# Audio_panel_board.net
KiCad netlist of a schematic drawn in EAGLE
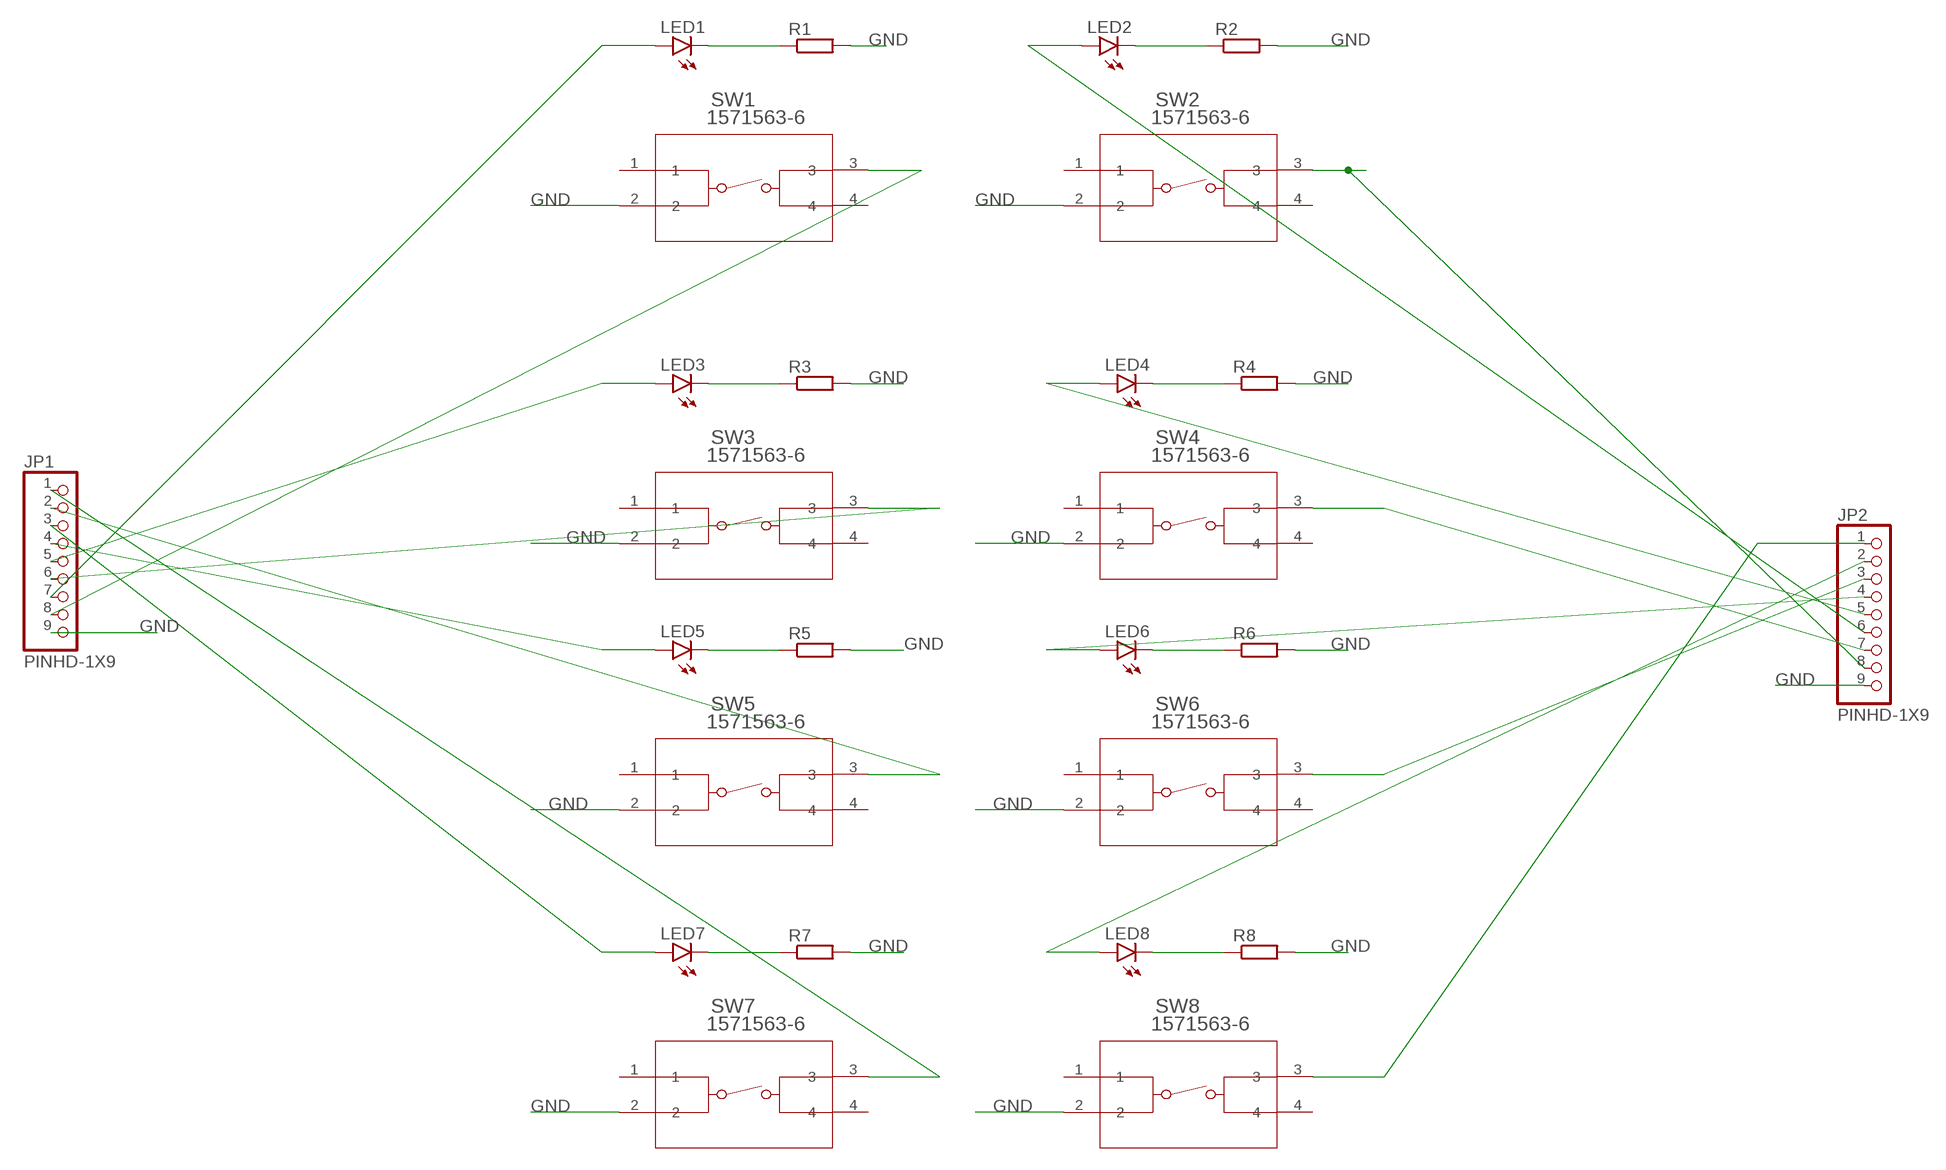
[diagram p0: schematic, sheet 1, part 1 of 2]
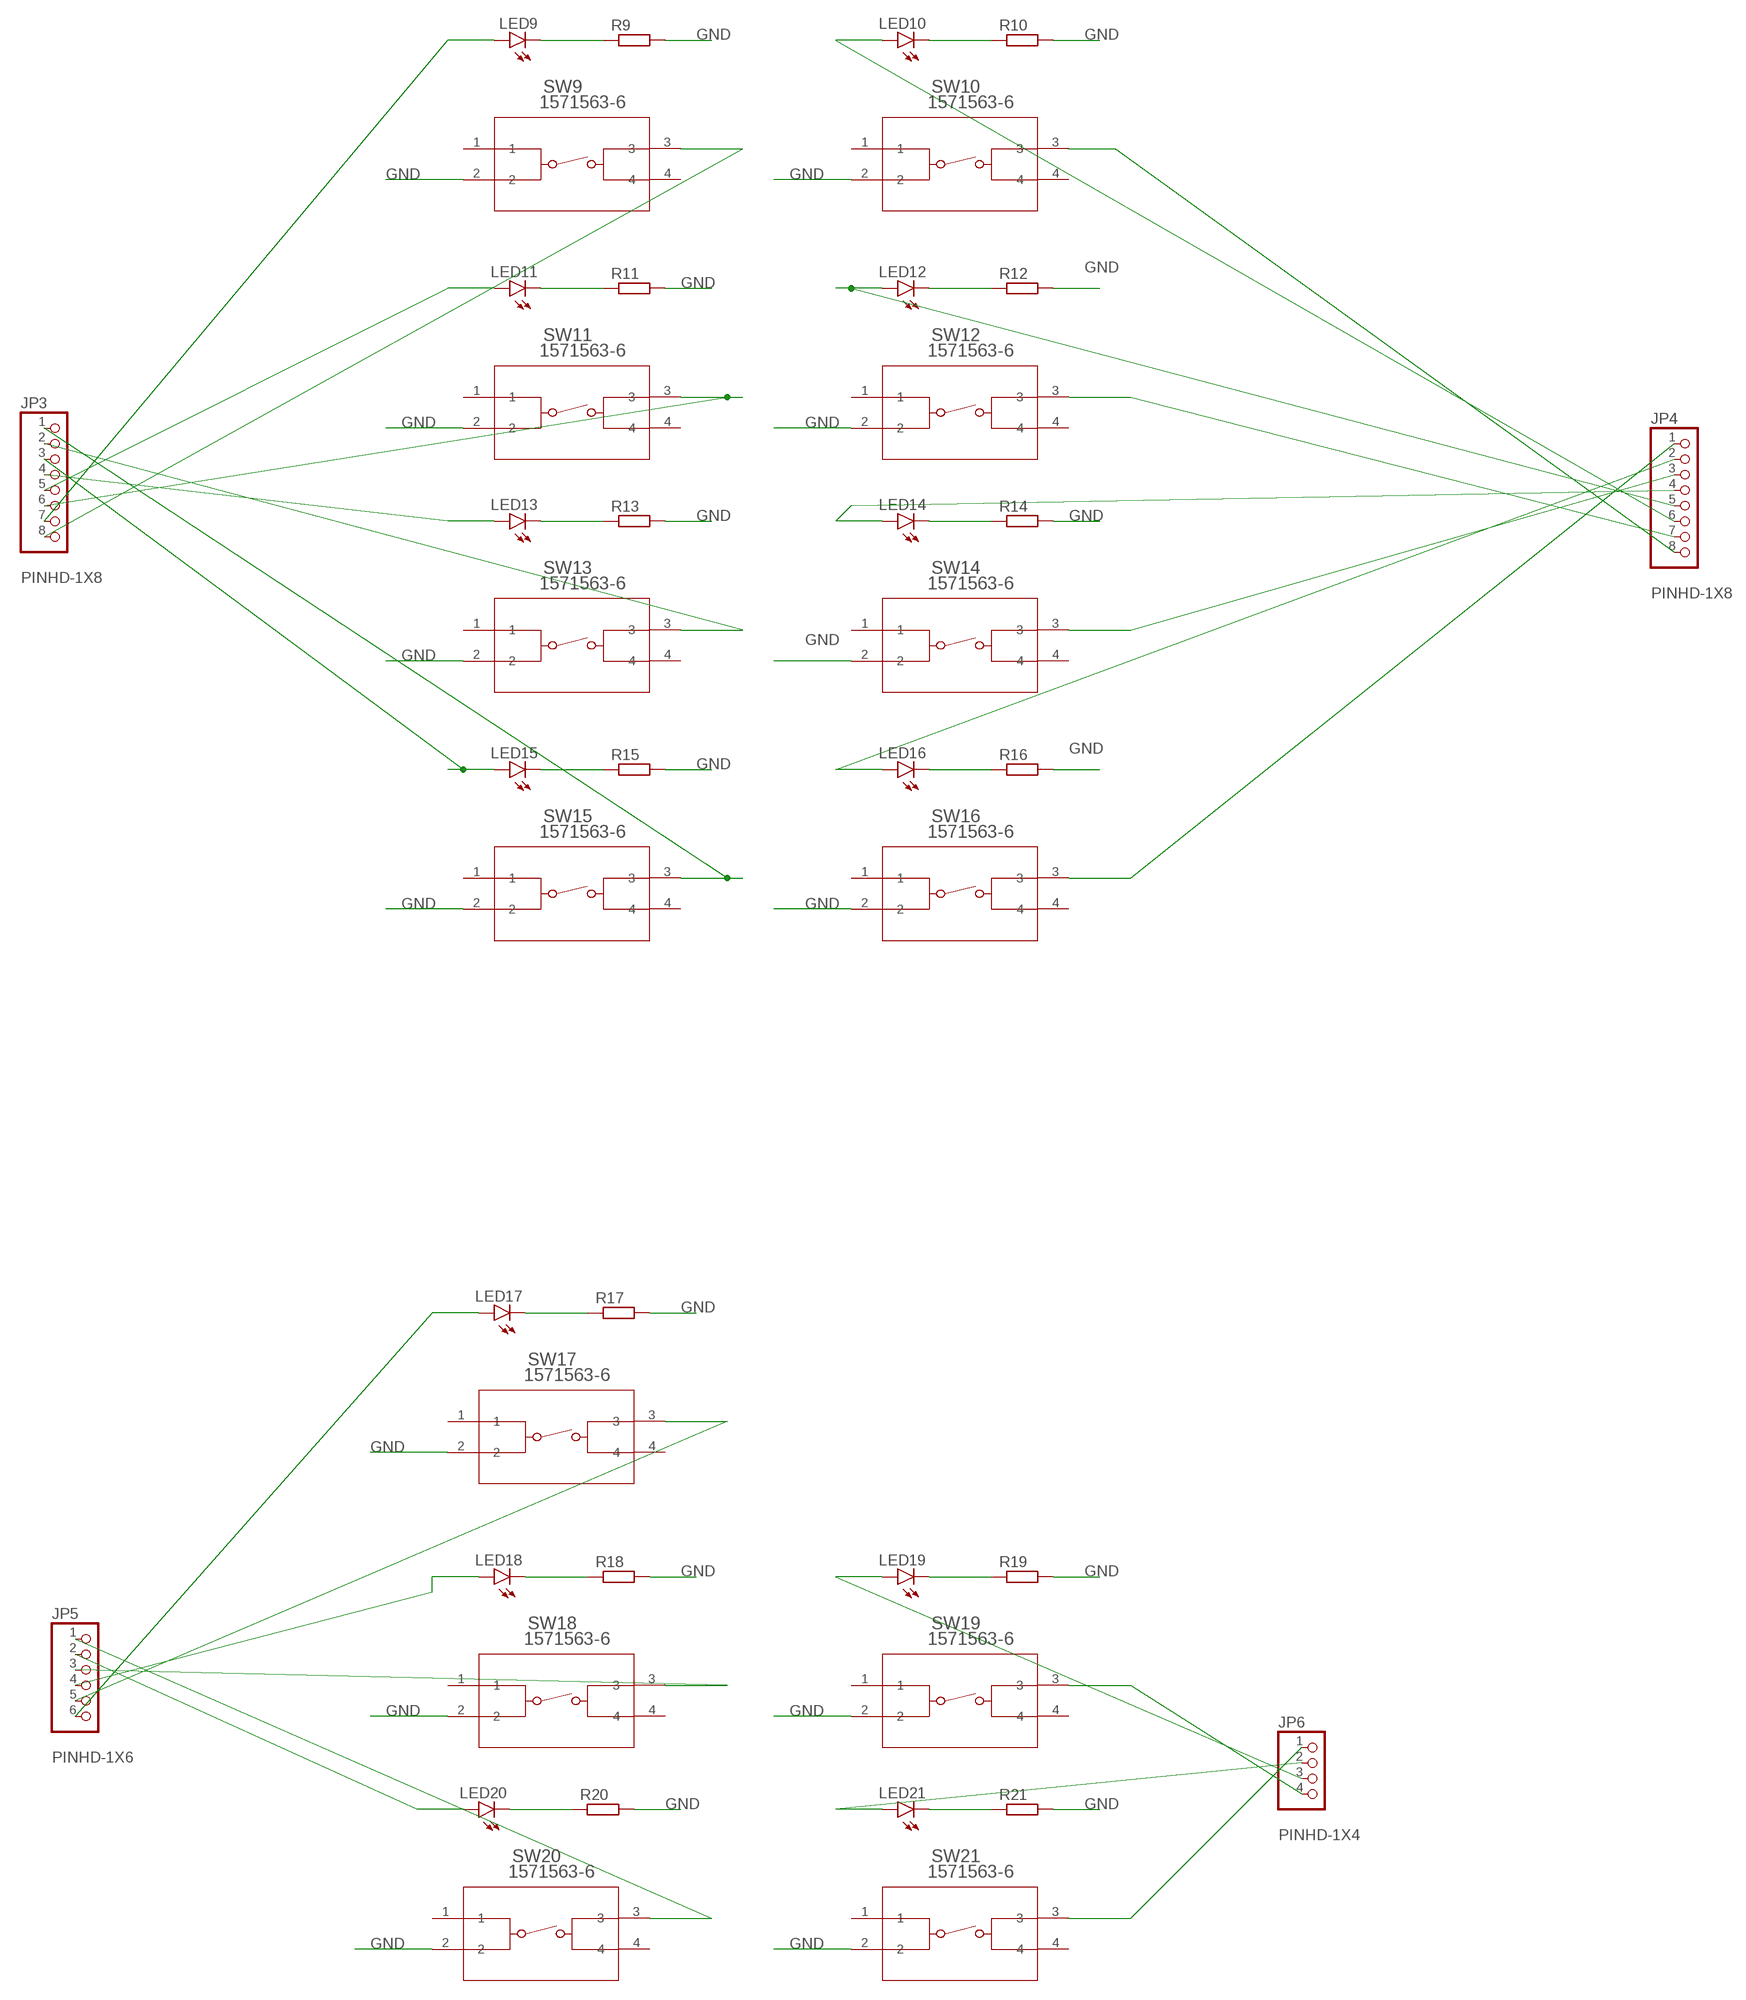
[diagram p1: schematic, sheet 1, part 2 of 2]

(export (version "E")
  (design (tool "Eeschema 10.0.6"))
  (components
    (comp (ref "JP1")
      (value "PINHD-1X9")
      (footprint "eagle-import:1X09")
      (libsource (lib "eagle-import") (part "PINHD-1X9"))
    )
    (comp (ref "JP2")
      (value "PINHD-1X9")
      (footprint "eagle-import:1X09")
      (libsource (lib "eagle-import") (part "PINHD-1X9"))
    )
    (comp (ref "JP3")
      (value "PINHD-1X8")
      (footprint "eagle-import:1X08")
      (libsource (lib "eagle-import") (part "PINHD-1X8"))
    )
    (comp (ref "JP4")
      (value "PINHD-1X8")
      (footprint "eagle-import:1X08")
      (libsource (lib "eagle-import") (part "PINHD-1X8"))
    )
    (comp (ref "JP5")
      (value "PINHD-1X6")
      (footprint "eagle-import:1X06")
      (libsource (lib "eagle-import") (part "PINHD-1X6"))
    )
    (comp (ref "JP6")
      (value "PINHD-1X4")
      (footprint "eagle-import:1X04")
      (libsource (lib "eagle-import") (part "PINHD-1X4"))
    )
    (comp (ref "LED1")
      (value "LEDCHIP-LED0805")
      (footprint "eagle-import:CHIP-LED0805")
      (libsource (lib "eagle-import") (part "LEDCHIP-LED0805"))
    )
    (comp (ref "LED2")
      (value "LEDCHIP-LED0805")
      (footprint "eagle-import:CHIP-LED0805")
      (libsource (lib "eagle-import") (part "LEDCHIP-LED0805"))
    )
    (comp (ref "LED3")
      (value "LEDCHIP-LED0805")
      (footprint "eagle-import:CHIP-LED0805")
      (libsource (lib "eagle-import") (part "LEDCHIP-LED0805"))
    )
    (comp (ref "LED4")
      (value "LEDCHIP-LED0805")
      (footprint "eagle-import:CHIP-LED0805")
      (libsource (lib "eagle-import") (part "LEDCHIP-LED0805"))
    )
    (comp (ref "LED5")
      (value "LEDCHIP-LED0805")
      (footprint "eagle-import:CHIP-LED0805")
      (libsource (lib "eagle-import") (part "LEDCHIP-LED0805"))
    )
    (comp (ref "LED6")
      (value "LEDCHIP-LED0805")
      (footprint "eagle-import:CHIP-LED0805")
      (libsource (lib "eagle-import") (part "LEDCHIP-LED0805"))
    )
    (comp (ref "LED7")
      (value "LEDCHIP-LED0805")
      (footprint "eagle-import:CHIP-LED0805")
      (libsource (lib "eagle-import") (part "LEDCHIP-LED0805"))
    )
    (comp (ref "LED8")
      (value "LEDCHIP-LED0805")
      (footprint "eagle-import:CHIP-LED0805")
      (libsource (lib "eagle-import") (part "LEDCHIP-LED0805"))
    )
    (comp (ref "LED9")
      (value "LEDCHIP-LED0805")
      (footprint "eagle-import:CHIP-LED0805")
      (libsource (lib "eagle-import") (part "LEDCHIP-LED0805"))
    )
    (comp (ref "LED10")
      (value "LEDCHIP-LED0805")
      (footprint "eagle-import:CHIP-LED0805")
      (libsource (lib "eagle-import") (part "LEDCHIP-LED0805"))
    )
    (comp (ref "LED11")
      (value "LEDCHIP-LED0805")
      (footprint "eagle-import:CHIP-LED0805")
      (libsource (lib "eagle-import") (part "LEDCHIP-LED0805"))
    )
    (comp (ref "LED12")
      (value "LEDCHIP-LED0805")
      (footprint "eagle-import:CHIP-LED0805")
      (libsource (lib "eagle-import") (part "LEDCHIP-LED0805"))
    )
    (comp (ref "LED13")
      (value "LEDCHIP-LED0805")
      (footprint "eagle-import:CHIP-LED0805")
      (libsource (lib "eagle-import") (part "LEDCHIP-LED0805"))
    )
    (comp (ref "LED14")
      (value "LEDCHIP-LED0805")
      (footprint "eagle-import:CHIP-LED0805")
      (libsource (lib "eagle-import") (part "LEDCHIP-LED0805"))
    )
    (comp (ref "LED15")
      (value "LEDCHIP-LED0805")
      (footprint "eagle-import:CHIP-LED0805")
      (libsource (lib "eagle-import") (part "LEDCHIP-LED0805"))
    )
    (comp (ref "LED16")
      (value "LEDCHIP-LED0805")
      (footprint "eagle-import:CHIP-LED0805")
      (libsource (lib "eagle-import") (part "LEDCHIP-LED0805"))
    )
    (comp (ref "LED17")
      (value "LEDCHIP-LED0805")
      (footprint "eagle-import:CHIP-LED0805")
      (libsource (lib "eagle-import") (part "LEDCHIP-LED0805"))
    )
    (comp (ref "LED18")
      (value "LEDCHIP-LED0805")
      (footprint "eagle-import:CHIP-LED0805")
      (libsource (lib "eagle-import") (part "LEDCHIP-LED0805"))
    )
    (comp (ref "LED19")
      (value "LEDCHIP-LED0805")
      (footprint "eagle-import:CHIP-LED0805")
      (libsource (lib "eagle-import") (part "LEDCHIP-LED0805"))
    )
    (comp (ref "LED20")
      (value "LEDCHIP-LED0805")
      (footprint "eagle-import:CHIP-LED0805")
      (libsource (lib "eagle-import") (part "LEDCHIP-LED0805"))
    )
    (comp (ref "LED21")
      (value "LEDCHIP-LED0805")
      (footprint "eagle-import:CHIP-LED0805")
      (libsource (lib "eagle-import") (part "LEDCHIP-LED0805"))
    )
    (comp (ref "R1")
      (value "R-EU_R1206")
      (footprint "eagle-import:R1206")
      (libsource (lib "eagle-import") (part "R-EU_R1206"))
    )
    (comp (ref "R2")
      (value "R-EU_R1206")
      (footprint "eagle-import:R1206")
      (libsource (lib "eagle-import") (part "R-EU_R1206"))
    )
    (comp (ref "R3")
      (value "R-EU_R1206")
      (footprint "eagle-import:R1206")
      (libsource (lib "eagle-import") (part "R-EU_R1206"))
    )
    (comp (ref "R4")
      (value "R-EU_R1206")
      (footprint "eagle-import:R1206")
      (libsource (lib "eagle-import") (part "R-EU_R1206"))
    )
    (comp (ref "R5")
      (value "R-EU_R1206")
      (footprint "eagle-import:R1206")
      (libsource (lib "eagle-import") (part "R-EU_R1206"))
    )
    (comp (ref "R6")
      (value "R-EU_R1206")
      (footprint "eagle-import:R1206")
      (libsource (lib "eagle-import") (part "R-EU_R1206"))
    )
    (comp (ref "R7")
      (value "R-EU_R1206")
      (footprint "eagle-import:R1206")
      (libsource (lib "eagle-import") (part "R-EU_R1206"))
    )
    (comp (ref "R8")
      (value "R-EU_R1206")
      (footprint "eagle-import:R1206")
      (libsource (lib "eagle-import") (part "R-EU_R1206"))
    )
    (comp (ref "R9")
      (value "R-EU_R1206")
      (footprint "eagle-import:R1206")
      (libsource (lib "eagle-import") (part "R-EU_R1206"))
    )
    (comp (ref "R10")
      (value "R-EU_R1206")
      (footprint "eagle-import:R1206")
      (libsource (lib "eagle-import") (part "R-EU_R1206"))
    )
    (comp (ref "R11")
      (value "R-EU_R1206")
      (footprint "eagle-import:R1206")
      (libsource (lib "eagle-import") (part "R-EU_R1206"))
    )
    (comp (ref "R12")
      (value "R-EU_R1206")
      (footprint "eagle-import:R1206")
      (libsource (lib "eagle-import") (part "R-EU_R1206"))
    )
    (comp (ref "R13")
      (value "R-EU_R1206")
      (footprint "eagle-import:R1206")
      (libsource (lib "eagle-import") (part "R-EU_R1206"))
    )
    (comp (ref "R14")
      (value "R-EU_R1206")
      (footprint "eagle-import:R1206")
      (libsource (lib "eagle-import") (part "R-EU_R1206"))
    )
    (comp (ref "R15")
      (value "R-EU_R1206")
      (footprint "eagle-import:R1206")
      (libsource (lib "eagle-import") (part "R-EU_R1206"))
    )
    (comp (ref "R16")
      (value "R-EU_R1206")
      (footprint "eagle-import:R1206")
      (libsource (lib "eagle-import") (part "R-EU_R1206"))
    )
    (comp (ref "R17")
      (value "R-EU_R1206")
      (footprint "eagle-import:R1206")
      (libsource (lib "eagle-import") (part "R-EU_R1206"))
    )
    (comp (ref "R18")
      (value "R-EU_R1206")
      (footprint "eagle-import:R1206")
      (libsource (lib "eagle-import") (part "R-EU_R1206"))
    )
    (comp (ref "R19")
      (value "R-EU_R1206")
      (footprint "eagle-import:R1206")
      (libsource (lib "eagle-import") (part "R-EU_R1206"))
    )
    (comp (ref "R20")
      (value "R-EU_R1206")
      (footprint "eagle-import:R1206")
      (libsource (lib "eagle-import") (part "R-EU_R1206"))
    )
    (comp (ref "R21")
      (value "R-EU_R1206")
      (footprint "eagle-import:R1206")
      (libsource (lib "eagle-import") (part "R-EU_R1206"))
    )
    (comp (ref "SW1")
      (value "1571563-6")
      (footprint "eagle-import:SW4_1437565-E")
      (fields (field (name "COPYRIGHT") "Copyright (C) 2016 Accelerated Designs. All rights reserved"))
      (libsource (lib "eagle-import") (part "1571563-6"))
    )
    (comp (ref "SW2")
      (value "1571563-6")
      (footprint "eagle-import:SW4_1437565-E")
      (fields (field (name "COPYRIGHT") "Copyright (C) 2016 Accelerated Designs. All rights reserved"))
      (libsource (lib "eagle-import") (part "1571563-6"))
    )
    (comp (ref "SW3")
      (value "1571563-6")
      (footprint "eagle-import:SW4_1437565-E")
      (fields (field (name "COPYRIGHT") "Copyright (C) 2016 Accelerated Designs. All rights reserved"))
      (libsource (lib "eagle-import") (part "1571563-6"))
    )
    (comp (ref "SW4")
      (value "1571563-6")
      (footprint "eagle-import:SW4_1437565-E")
      (fields (field (name "COPYRIGHT") "Copyright (C) 2016 Accelerated Designs. All rights reserved"))
      (libsource (lib "eagle-import") (part "1571563-6"))
    )
    (comp (ref "SW5")
      (value "1571563-6")
      (footprint "eagle-import:SW4_1437565-E")
      (fields (field (name "COPYRIGHT") "Copyright (C) 2016 Accelerated Designs. All rights reserved"))
      (libsource (lib "eagle-import") (part "1571563-6"))
    )
    (comp (ref "SW6")
      (value "1571563-6")
      (footprint "eagle-import:SW4_1437565-E")
      (fields (field (name "COPYRIGHT") "Copyright (C) 2016 Accelerated Designs. All rights reserved"))
      (libsource (lib "eagle-import") (part "1571563-6"))
    )
    (comp (ref "SW7")
      (value "1571563-6")
      (footprint "eagle-import:SW4_1437565-E")
      (fields (field (name "COPYRIGHT") "Copyright (C) 2016 Accelerated Designs. All rights reserved"))
      (libsource (lib "eagle-import") (part "1571563-6"))
    )
    (comp (ref "SW8")
      (value "1571563-6")
      (footprint "eagle-import:SW4_1437565-E")
      (fields (field (name "COPYRIGHT") "Copyright (C) 2016 Accelerated Designs. All rights reserved"))
      (libsource (lib "eagle-import") (part "1571563-6"))
    )
    (comp (ref "SW9")
      (value "1571563-6")
      (footprint "eagle-import:SW4_1437565-E")
      (fields (field (name "COPYRIGHT") "Copyright (C) 2016 Accelerated Designs. All rights reserved"))
      (libsource (lib "eagle-import") (part "1571563-6"))
    )
    (comp (ref "SW10")
      (value "1571563-6")
      (footprint "eagle-import:SW4_1437565-E")
      (fields (field (name "COPYRIGHT") "Copyright (C) 2016 Accelerated Designs. All rights reserved"))
      (libsource (lib "eagle-import") (part "1571563-6"))
    )
    (comp (ref "SW11")
      (value "1571563-6")
      (footprint "eagle-import:SW4_1437565-E")
      (fields (field (name "COPYRIGHT") "Copyright (C) 2016 Accelerated Designs. All rights reserved"))
      (libsource (lib "eagle-import") (part "1571563-6"))
    )
    (comp (ref "SW12")
      (value "1571563-6")
      (footprint "eagle-import:SW4_1437565-E")
      (fields (field (name "COPYRIGHT") "Copyright (C) 2016 Accelerated Designs. All rights reserved"))
      (libsource (lib "eagle-import") (part "1571563-6"))
    )
    (comp (ref "SW13")
      (value "1571563-6")
      (footprint "eagle-import:SW4_1437565-E")
      (fields (field (name "COPYRIGHT") "Copyright (C) 2016 Accelerated Designs. All rights reserved"))
      (libsource (lib "eagle-import") (part "1571563-6"))
    )
    (comp (ref "SW14")
      (value "1571563-6")
      (footprint "eagle-import:SW4_1437565-E")
      (fields (field (name "COPYRIGHT") "Copyright (C) 2016 Accelerated Designs. All rights reserved"))
      (libsource (lib "eagle-import") (part "1571563-6"))
    )
    (comp (ref "SW15")
      (value "1571563-6")
      (footprint "eagle-import:SW4_1437565-E")
      (fields (field (name "COPYRIGHT") "Copyright (C) 2016 Accelerated Designs. All rights reserved"))
      (libsource (lib "eagle-import") (part "1571563-6"))
    )
    (comp (ref "SW16")
      (value "1571563-6")
      (footprint "eagle-import:SW4_1437565-E")
      (fields (field (name "COPYRIGHT") "Copyright (C) 2016 Accelerated Designs. All rights reserved"))
      (libsource (lib "eagle-import") (part "1571563-6"))
    )
    (comp (ref "SW17")
      (value "1571563-6")
      (footprint "eagle-import:SW4_1437565-E")
      (fields (field (name "COPYRIGHT") "Copyright (C) 2016 Accelerated Designs. All rights reserved"))
      (libsource (lib "eagle-import") (part "1571563-6"))
    )
    (comp (ref "SW18")
      (value "1571563-6")
      (footprint "eagle-import:SW4_1437565-E")
      (fields (field (name "COPYRIGHT") "Copyright (C) 2016 Accelerated Designs. All rights reserved"))
      (libsource (lib "eagle-import") (part "1571563-6"))
    )
    (comp (ref "SW19")
      (value "1571563-6")
      (footprint "eagle-import:SW4_1437565-E")
      (fields (field (name "COPYRIGHT") "Copyright (C) 2016 Accelerated Designs. All rights reserved"))
      (libsource (lib "eagle-import") (part "1571563-6"))
    )
    (comp (ref "SW20")
      (value "1571563-6")
      (footprint "eagle-import:SW4_1437565-E")
      (fields (field (name "COPYRIGHT") "Copyright (C) 2016 Accelerated Designs. All rights reserved"))
      (libsource (lib "eagle-import") (part "1571563-6"))
    )
    (comp (ref "SW21")
      (value "1571563-6")
      (footprint "eagle-import:SW4_1437565-E")
      (fields (field (name "COPYRIGHT") "Copyright (C) 2016 Accelerated Designs. All rights reserved"))
      (libsource (lib "eagle-import") (part "1571563-6"))
    )
  )
  (nets
    (net (code "1") (name "/GND") (class "Default")
      (node (ref "JP1") (pin "9") (pinfunction "9_9") (pintype "passive"))
      (node (ref "JP2") (pin "9") (pinfunction "9_9") (pintype "passive"))
      (node (ref "R1") (pin "2") (pinfunction "2_2") (pintype "passive"))
      (node (ref "R10") (pin "2") (pinfunction "2_2") (pintype "passive"))
      (node (ref "R11") (pin "2") (pinfunction "2_2") (pintype "passive"))
      (node (ref "R12") (pin "2") (pinfunction "2_2") (pintype "passive"))
      (node (ref "R13") (pin "2") (pinfunction "2_2") (pintype "passive"))
      (node (ref "R14") (pin "2") (pinfunction "2_2") (pintype "passive"))
      (node (ref "R15") (pin "2") (pinfunction "2_2") (pintype "passive"))
      (node (ref "R16") (pin "2") (pinfunction "2_2") (pintype "passive"))
      (node (ref "R17") (pin "2") (pinfunction "2_2") (pintype "passive"))
      (node (ref "R18") (pin "2") (pinfunction "2_2") (pintype "passive"))
      (node (ref "R19") (pin "2") (pinfunction "2_2") (pintype "passive"))
      (node (ref "R2") (pin "2") (pinfunction "2_2") (pintype "passive"))
      (node (ref "R20") (pin "2") (pinfunction "2_2") (pintype "passive"))
      (node (ref "R21") (pin "2") (pinfunction "2_2") (pintype "passive"))
      (node (ref "R3") (pin "2") (pinfunction "2_2") (pintype "passive"))
      (node (ref "R4") (pin "2") (pinfunction "2_2") (pintype "passive"))
      (node (ref "R5") (pin "2") (pinfunction "2_2") (pintype "passive"))
      (node (ref "R6") (pin "2") (pinfunction "2_2") (pintype "passive"))
      (node (ref "R7") (pin "2") (pinfunction "2_2") (pintype "passive"))
      (node (ref "R8") (pin "2") (pinfunction "2_2") (pintype "passive"))
      (node (ref "R9") (pin "2") (pinfunction "2_2") (pintype "passive"))
      (node (ref "SW1") (pin "2") (pinfunction "2_2") (pintype "passive"))
      (node (ref "SW10") (pin "2") (pinfunction "2_2") (pintype "passive"))
      (node (ref "SW11") (pin "2") (pinfunction "2_2") (pintype "passive"))
      (node (ref "SW12") (pin "2") (pinfunction "2_2") (pintype "passive"))
      (node (ref "SW13") (pin "2") (pinfunction "2_2") (pintype "passive"))
      (node (ref "SW14") (pin "2") (pinfunction "2_2") (pintype "passive"))
      (node (ref "SW15") (pin "2") (pinfunction "2_2") (pintype "passive"))
      (node (ref "SW16") (pin "2") (pinfunction "2_2") (pintype "passive"))
      (node (ref "SW17") (pin "2") (pinfunction "2_2") (pintype "passive"))
      (node (ref "SW18") (pin "2") (pinfunction "2_2") (pintype "passive"))
      (node (ref "SW19") (pin "2") (pinfunction "2_2") (pintype "passive"))
      (node (ref "SW2") (pin "2") (pinfunction "2_2") (pintype "passive"))
      (node (ref "SW20") (pin "2") (pinfunction "2_2") (pintype "passive"))
      (node (ref "SW21") (pin "2") (pinfunction "2_2") (pintype "passive"))
      (node (ref "SW3") (pin "2") (pinfunction "2_2") (pintype "passive"))
      (node (ref "SW4") (pin "2") (pinfunction "2_2") (pintype "passive"))
      (node (ref "SW5") (pin "2") (pinfunction "2_2") (pintype "passive"))
      (node (ref "SW6") (pin "2") (pinfunction "2_2") (pintype "passive"))
      (node (ref "SW7") (pin "2") (pinfunction "2_2") (pintype "passive"))
      (node (ref "SW8") (pin "2") (pinfunction "2_2") (pintype "passive"))
      (node (ref "SW9") (pin "2") (pinfunction "2_2") (pintype "passive"))
    )
    (net (code "2") (name "Net-(JP1-Pad1)") (class "Default")
      (node (ref "JP1") (pin "1") (pinfunction "1_1") (pintype "passive"))
      (node (ref "SW7") (pin "3") (pinfunction "3_3") (pintype "passive"))
    )
    (net (code "3") (name "Net-(JP1-Pad2)") (class "Default")
      (node (ref "JP1") (pin "2") (pinfunction "2_2") (pintype "passive"))
      (node (ref "SW5") (pin "3") (pinfunction "3_3") (pintype "passive"))
    )
    (net (code "4") (name "Net-(JP1-Pad3)") (class "Default")
      (node (ref "JP1") (pin "3") (pinfunction "3_3") (pintype "passive"))
      (node (ref "LED7") (pin "A") (pinfunction "A_A") (pintype "passive"))
    )
    (net (code "5") (name "Net-(JP1-Pad4)") (class "Default")
      (node (ref "JP1") (pin "4") (pinfunction "4_4") (pintype "passive"))
      (node (ref "LED5") (pin "A") (pinfunction "A_A") (pintype "passive"))
    )
    (net (code "6") (name "Net-(JP1-Pad5)") (class "Default")
      (node (ref "JP1") (pin "5") (pinfunction "5_5") (pintype "passive"))
      (node (ref "LED3") (pin "A") (pinfunction "A_A") (pintype "passive"))
    )
    (net (code "7") (name "Net-(JP1-Pad6)") (class "Default")
      (node (ref "JP1") (pin "6") (pinfunction "6_6") (pintype "passive"))
      (node (ref "SW3") (pin "3") (pinfunction "3_3") (pintype "passive"))
    )
    (net (code "8") (name "Net-(JP1-Pad7)") (class "Default")
      (node (ref "JP1") (pin "7") (pinfunction "7_7") (pintype "passive"))
      (node (ref "LED1") (pin "A") (pinfunction "A_A") (pintype "passive"))
    )
    (net (code "9") (name "Net-(JP1-Pad8)") (class "Default")
      (node (ref "JP1") (pin "8") (pinfunction "8_8") (pintype "passive"))
      (node (ref "SW1") (pin "3") (pinfunction "3_3") (pintype "passive"))
    )
    (net (code "10") (name "Net-(JP2-Pad1)") (class "Default")
      (node (ref "JP2") (pin "1") (pinfunction "1_1") (pintype "passive"))
      (node (ref "SW8") (pin "3") (pinfunction "3_3") (pintype "passive"))
    )
    (net (code "11") (name "Net-(JP2-Pad2)") (class "Default")
      (node (ref "JP2") (pin "2") (pinfunction "2_2") (pintype "passive"))
      (node (ref "LED8") (pin "A") (pinfunction "A_A") (pintype "passive"))
    )
    (net (code "12") (name "Net-(JP2-Pad3)") (class "Default")
      (node (ref "JP2") (pin "3") (pinfunction "3_3") (pintype "passive"))
      (node (ref "SW6") (pin "3") (pinfunction "3_3") (pintype "passive"))
    )
    (net (code "13") (name "Net-(JP2-Pad4)") (class "Default")
      (node (ref "JP2") (pin "4") (pinfunction "4_4") (pintype "passive"))
      (node (ref "LED6") (pin "A") (pinfunction "A_A") (pintype "passive"))
    )
    (net (code "14") (name "Net-(JP2-Pad5)") (class "Default")
      (node (ref "JP2") (pin "5") (pinfunction "5_5") (pintype "passive"))
      (node (ref "LED4") (pin "A") (pinfunction "A_A") (pintype "passive"))
    )
    (net (code "15") (name "Net-(JP2-Pad6)") (class "Default")
      (node (ref "JP2") (pin "6") (pinfunction "6_6") (pintype "passive"))
      (node (ref "LED2") (pin "A") (pinfunction "A_A") (pintype "passive"))
    )
    (net (code "16") (name "Net-(JP2-Pad7)") (class "Default")
      (node (ref "JP2") (pin "7") (pinfunction "7_7") (pintype "passive"))
      (node (ref "SW4") (pin "3") (pinfunction "3_3") (pintype "passive"))
    )
    (net (code "17") (name "Net-(JP2-Pad8)") (class "Default")
      (node (ref "JP2") (pin "8") (pinfunction "8_8") (pintype "passive"))
      (node (ref "SW2") (pin "3") (pinfunction "3_3") (pintype "passive"))
    )
    (net (code "18") (name "Net-(JP3-Pad1)") (class "Default")
      (node (ref "JP3") (pin "1") (pinfunction "1_1") (pintype "passive"))
      (node (ref "SW15") (pin "3") (pinfunction "3_3") (pintype "passive"))
    )
    (net (code "19") (name "Net-(JP3-Pad2)") (class "Default")
      (node (ref "JP3") (pin "2") (pinfunction "2_2") (pintype "passive"))
      (node (ref "SW13") (pin "3") (pinfunction "3_3") (pintype "passive"))
    )
    (net (code "20") (name "Net-(JP3-Pad3)") (class "Default")
      (node (ref "JP3") (pin "3") (pinfunction "3_3") (pintype "passive"))
      (node (ref "LED15") (pin "A") (pinfunction "A_A") (pintype "passive"))
    )
    (net (code "21") (name "Net-(JP3-Pad4)") (class "Default")
      (node (ref "JP3") (pin "4") (pinfunction "4_4") (pintype "passive"))
      (node (ref "LED13") (pin "A") (pinfunction "A_A") (pintype "passive"))
    )
    (net (code "22") (name "Net-(JP3-Pad5)") (class "Default")
      (node (ref "JP3") (pin "5") (pinfunction "5_5") (pintype "passive"))
      (node (ref "LED11") (pin "A") (pinfunction "A_A") (pintype "passive"))
    )
    (net (code "23") (name "Net-(JP3-Pad6)") (class "Default")
      (node (ref "JP3") (pin "6") (pinfunction "6_6") (pintype "passive"))
      (node (ref "SW11") (pin "3") (pinfunction "3_3") (pintype "passive"))
    )
    (net (code "24") (name "Net-(JP3-Pad7)") (class "Default")
      (node (ref "JP3") (pin "7") (pinfunction "7_7") (pintype "passive"))
      (node (ref "LED9") (pin "A") (pinfunction "A_A") (pintype "passive"))
    )
    (net (code "25") (name "Net-(JP3-Pad8)") (class "Default")
      (node (ref "JP3") (pin "8") (pinfunction "8_8") (pintype "passive"))
      (node (ref "SW9") (pin "3") (pinfunction "3_3") (pintype "passive"))
    )
    (net (code "26") (name "Net-(JP4-Pad1)") (class "Default")
      (node (ref "JP4") (pin "1") (pinfunction "1_1") (pintype "passive"))
      (node (ref "SW16") (pin "3") (pinfunction "3_3") (pintype "passive"))
    )
    (net (code "27") (name "Net-(JP4-Pad2)") (class "Default")
      (node (ref "JP4") (pin "2") (pinfunction "2_2") (pintype "passive"))
      (node (ref "LED16") (pin "A") (pinfunction "A_A") (pintype "passive"))
    )
    (net (code "28") (name "Net-(JP4-Pad3)") (class "Default")
      (node (ref "JP4") (pin "3") (pinfunction "3_3") (pintype "passive"))
      (node (ref "SW14") (pin "3") (pinfunction "3_3") (pintype "passive"))
    )
    (net (code "29") (name "Net-(JP4-Pad4)") (class "Default")
      (node (ref "JP4") (pin "4") (pinfunction "4_4") (pintype "passive"))
      (node (ref "LED14") (pin "A") (pinfunction "A_A") (pintype "passive"))
    )
    (net (code "30") (name "Net-(JP4-Pad5)") (class "Default")
      (node (ref "JP4") (pin "5") (pinfunction "5_5") (pintype "passive"))
      (node (ref "LED12") (pin "A") (pinfunction "A_A") (pintype "passive"))
    )
    (net (code "31") (name "Net-(JP4-Pad6)") (class "Default")
      (node (ref "JP4") (pin "6") (pinfunction "6_6") (pintype "passive"))
      (node (ref "LED10") (pin "A") (pinfunction "A_A") (pintype "passive"))
    )
    (net (code "32") (name "Net-(JP4-Pad7)") (class "Default")
      (node (ref "JP4") (pin "7") (pinfunction "7_7") (pintype "passive"))
      (node (ref "SW12") (pin "3") (pinfunction "3_3") (pintype "passive"))
    )
    (net (code "33") (name "Net-(JP4-Pad8)") (class "Default")
      (node (ref "JP4") (pin "8") (pinfunction "8_8") (pintype "passive"))
      (node (ref "SW10") (pin "3") (pinfunction "3_3") (pintype "passive"))
    )
    (net (code "34") (name "Net-(JP5-Pad1)") (class "Default")
      (node (ref "JP5") (pin "1") (pinfunction "1_1") (pintype "passive"))
      (node (ref "SW20") (pin "3") (pinfunction "3_3") (pintype "passive"))
    )
    (net (code "35") (name "Net-(JP5-Pad2)") (class "Default")
      (node (ref "JP5") (pin "2") (pinfunction "2_2") (pintype "passive"))
      (node (ref "LED20") (pin "A") (pinfunction "A_A") (pintype "passive"))
    )
    (net (code "36") (name "Net-(JP5-Pad3)") (class "Default")
      (node (ref "JP5") (pin "3") (pinfunction "3_3") (pintype "passive"))
      (node (ref "SW18") (pin "3") (pinfunction "3_3") (pintype "passive"))
    )
    (net (code "37") (name "Net-(JP5-Pad4)") (class "Default")
      (node (ref "JP5") (pin "4") (pinfunction "4_4") (pintype "passive"))
      (node (ref "LED18") (pin "A") (pinfunction "A_A") (pintype "passive"))
    )
    (net (code "38") (name "Net-(JP5-Pad5)") (class "Default")
      (node (ref "JP5") (pin "5") (pinfunction "5_5") (pintype "passive"))
      (node (ref "SW17") (pin "3") (pinfunction "3_3") (pintype "passive"))
    )
    (net (code "39") (name "Net-(JP5-Pad6)") (class "Default")
      (node (ref "JP5") (pin "6") (pinfunction "6_6") (pintype "passive"))
      (node (ref "LED17") (pin "A") (pinfunction "A_A") (pintype "passive"))
    )
    (net (code "40") (name "Net-(JP6-Pad1)") (class "Default")
      (node (ref "JP6") (pin "1") (pinfunction "1_1") (pintype "passive"))
      (node (ref "SW21") (pin "3") (pinfunction "3_3") (pintype "passive"))
    )
    (net (code "41") (name "Net-(JP6-Pad2)") (class "Default")
      (node (ref "JP6") (pin "2") (pinfunction "2_2") (pintype "passive"))
      (node (ref "LED21") (pin "A") (pinfunction "A_A") (pintype "passive"))
    )
    (net (code "42") (name "Net-(JP6-Pad3)") (class "Default")
      (node (ref "JP6") (pin "3") (pinfunction "3_3") (pintype "passive"))
      (node (ref "LED19") (pin "A") (pinfunction "A_A") (pintype "passive"))
    )
    (net (code "43") (name "Net-(JP6-Pad4)") (class "Default")
      (node (ref "JP6") (pin "4") (pinfunction "4_4") (pintype "passive"))
      (node (ref "SW19") (pin "3") (pinfunction "3_3") (pintype "passive"))
    )
    (net (code "44") (name "Net-(LED1-PadC)") (class "Default")
      (node (ref "LED1") (pin "C") (pinfunction "C_C") (pintype "passive"))
      (node (ref "R1") (pin "1") (pinfunction "1_1") (pintype "passive"))
    )
    (net (code "45") (name "Net-(LED2-PadC)") (class "Default")
      (node (ref "LED2") (pin "C") (pinfunction "C_C") (pintype "passive"))
      (node (ref "R2") (pin "1") (pinfunction "1_1") (pintype "passive"))
    )
    (net (code "46") (name "Net-(LED3-PadC)") (class "Default")
      (node (ref "LED3") (pin "C") (pinfunction "C_C") (pintype "passive"))
      (node (ref "R3") (pin "1") (pinfunction "1_1") (pintype "passive"))
    )
    (net (code "47") (name "Net-(LED4-PadC)") (class "Default")
      (node (ref "LED4") (pin "C") (pinfunction "C_C") (pintype "passive"))
      (node (ref "R4") (pin "1") (pinfunction "1_1") (pintype "passive"))
    )
    (net (code "48") (name "Net-(LED5-PadC)") (class "Default")
      (node (ref "LED5") (pin "C") (pinfunction "C_C") (pintype "passive"))
      (node (ref "R5") (pin "1") (pinfunction "1_1") (pintype "passive"))
    )
    (net (code "49") (name "Net-(LED6-PadC)") (class "Default")
      (node (ref "LED6") (pin "C") (pinfunction "C_C") (pintype "passive"))
      (node (ref "R6") (pin "1") (pinfunction "1_1") (pintype "passive"))
    )
    (net (code "50") (name "Net-(LED7-PadC)") (class "Default")
      (node (ref "LED7") (pin "C") (pinfunction "C_C") (pintype "passive"))
      (node (ref "R7") (pin "1") (pinfunction "1_1") (pintype "passive"))
    )
    (net (code "51") (name "Net-(LED8-PadC)") (class "Default")
      (node (ref "LED8") (pin "C") (pinfunction "C_C") (pintype "passive"))
      (node (ref "R8") (pin "1") (pinfunction "1_1") (pintype "passive"))
    )
    (net (code "52") (name "Net-(LED9-PadC)") (class "Default")
      (node (ref "LED9") (pin "C") (pinfunction "C_C") (pintype "passive"))
      (node (ref "R9") (pin "1") (pinfunction "1_1") (pintype "passive"))
    )
    (net (code "53") (name "Net-(LED10-PadC)") (class "Default")
      (node (ref "LED10") (pin "C") (pinfunction "C_C") (pintype "passive"))
      (node (ref "R10") (pin "1") (pinfunction "1_1") (pintype "passive"))
    )
    (net (code "54") (name "Net-(LED11-PadC)") (class "Default")
      (node (ref "LED11") (pin "C") (pinfunction "C_C") (pintype "passive"))
      (node (ref "R11") (pin "1") (pinfunction "1_1") (pintype "passive"))
    )
    (net (code "55") (name "Net-(LED12-PadC)") (class "Default")
      (node (ref "LED12") (pin "C") (pinfunction "C_C") (pintype "passive"))
      (node (ref "R12") (pin "1") (pinfunction "1_1") (pintype "passive"))
    )
    (net (code "56") (name "Net-(LED13-PadC)") (class "Default")
      (node (ref "LED13") (pin "C") (pinfunction "C_C") (pintype "passive"))
      (node (ref "R13") (pin "1") (pinfunction "1_1") (pintype "passive"))
    )
    (net (code "57") (name "Net-(LED14-PadC)") (class "Default")
      (node (ref "LED14") (pin "C") (pinfunction "C_C") (pintype "passive"))
      (node (ref "R14") (pin "1") (pinfunction "1_1") (pintype "passive"))
    )
    (net (code "58") (name "Net-(LED15-PadC)") (class "Default")
      (node (ref "LED15") (pin "C") (pinfunction "C_C") (pintype "passive"))
      (node (ref "R15") (pin "1") (pinfunction "1_1") (pintype "passive"))
    )
    (net (code "59") (name "Net-(LED16-PadC)") (class "Default")
      (node (ref "LED16") (pin "C") (pinfunction "C_C") (pintype "passive"))
      (node (ref "R16") (pin "1") (pinfunction "1_1") (pintype "passive"))
    )
    (net (code "60") (name "Net-(LED17-PadC)") (class "Default")
      (node (ref "LED17") (pin "C") (pinfunction "C_C") (pintype "passive"))
      (node (ref "R17") (pin "1") (pinfunction "1_1") (pintype "passive"))
    )
    (net (code "61") (name "Net-(LED18-PadC)") (class "Default")
      (node (ref "LED18") (pin "C") (pinfunction "C_C") (pintype "passive"))
      (node (ref "R18") (pin "1") (pinfunction "1_1") (pintype "passive"))
    )
    (net (code "62") (name "Net-(LED19-PadC)") (class "Default")
      (node (ref "LED19") (pin "C") (pinfunction "C_C") (pintype "passive"))
      (node (ref "R19") (pin "1") (pinfunction "1_1") (pintype "passive"))
    )
    (net (code "63") (name "Net-(LED20-PadC)") (class "Default")
      (node (ref "LED20") (pin "C") (pinfunction "C_C") (pintype "passive"))
      (node (ref "R20") (pin "1") (pinfunction "1_1") (pintype "passive"))
    )
    (net (code "64") (name "Net-(LED21-PadC)") (class "Default")
      (node (ref "LED21") (pin "C") (pinfunction "C_C") (pintype "passive"))
      (node (ref "R21") (pin "1") (pinfunction "1_1") (pintype "passive"))
    )
    (net (code "65") (name "unconnected-(SW1-Pad1)") (class "Default")
      (node (ref "SW1") (pin "1") (pinfunction "1_1") (pintype "passive"))
    )
    (net (code "66") (name "unconnected-(SW1-Pad4)") (class "Default")
      (node (ref "SW1") (pin "4") (pinfunction "4_4") (pintype "passive"))
    )
    (net (code "67") (name "unconnected-(SW2-Pad1)") (class "Default")
      (node (ref "SW2") (pin "1") (pinfunction "1_1") (pintype "passive"))
    )
    (net (code "68") (name "unconnected-(SW2-Pad4)") (class "Default")
      (node (ref "SW2") (pin "4") (pinfunction "4_4") (pintype "passive"))
    )
    (net (code "69") (name "unconnected-(SW3-Pad1)") (class "Default")
      (node (ref "SW3") (pin "1") (pinfunction "1_1") (pintype "passive"))
    )
    (net (code "70") (name "unconnected-(SW3-Pad4)") (class "Default")
      (node (ref "SW3") (pin "4") (pinfunction "4_4") (pintype "passive"))
    )
    (net (code "71") (name "unconnected-(SW4-Pad1)") (class "Default")
      (node (ref "SW4") (pin "1") (pinfunction "1_1") (pintype "passive"))
    )
    (net (code "72") (name "unconnected-(SW4-Pad4)") (class "Default")
      (node (ref "SW4") (pin "4") (pinfunction "4_4") (pintype "passive"))
    )
    (net (code "73") (name "unconnected-(SW5-Pad1)") (class "Default")
      (node (ref "SW5") (pin "1") (pinfunction "1_1") (pintype "passive"))
    )
    (net (code "74") (name "unconnected-(SW5-Pad4)") (class "Default")
      (node (ref "SW5") (pin "4") (pinfunction "4_4") (pintype "passive"))
    )
    (net (code "75") (name "unconnected-(SW6-Pad1)") (class "Default")
      (node (ref "SW6") (pin "1") (pinfunction "1_1") (pintype "passive"))
    )
    (net (code "76") (name "unconnected-(SW6-Pad4)") (class "Default")
      (node (ref "SW6") (pin "4") (pinfunction "4_4") (pintype "passive"))
    )
    (net (code "77") (name "unconnected-(SW7-Pad1)") (class "Default")
      (node (ref "SW7") (pin "1") (pinfunction "1_1") (pintype "passive"))
    )
    (net (code "78") (name "unconnected-(SW7-Pad4)") (class "Default")
      (node (ref "SW7") (pin "4") (pinfunction "4_4") (pintype "passive"))
    )
    (net (code "79") (name "unconnected-(SW8-Pad1)") (class "Default")
      (node (ref "SW8") (pin "1") (pinfunction "1_1") (pintype "passive"))
    )
    (net (code "80") (name "unconnected-(SW8-Pad4)") (class "Default")
      (node (ref "SW8") (pin "4") (pinfunction "4_4") (pintype "passive"))
    )
    (net (code "81") (name "unconnected-(SW9-Pad1)") (class "Default")
      (node (ref "SW9") (pin "1") (pinfunction "1_1") (pintype "passive"))
    )
    (net (code "82") (name "unconnected-(SW9-Pad4)") (class "Default")
      (node (ref "SW9") (pin "4") (pinfunction "4_4") (pintype "passive"))
    )
    (net (code "83") (name "unconnected-(SW10-Pad1)") (class "Default")
      (node (ref "SW10") (pin "1") (pinfunction "1_1") (pintype "passive"))
    )
    (net (code "84") (name "unconnected-(SW10-Pad4)") (class "Default")
      (node (ref "SW10") (pin "4") (pinfunction "4_4") (pintype "passive"))
    )
    (net (code "85") (name "unconnected-(SW11-Pad1)") (class "Default")
      (node (ref "SW11") (pin "1") (pinfunction "1_1") (pintype "passive"))
    )
    (net (code "86") (name "unconnected-(SW11-Pad4)") (class "Default")
      (node (ref "SW11") (pin "4") (pinfunction "4_4") (pintype "passive"))
    )
    (net (code "87") (name "unconnected-(SW12-Pad1)") (class "Default")
      (node (ref "SW12") (pin "1") (pinfunction "1_1") (pintype "passive"))
    )
    (net (code "88") (name "unconnected-(SW12-Pad4)") (class "Default")
      (node (ref "SW12") (pin "4") (pinfunction "4_4") (pintype "passive"))
    )
    (net (code "89") (name "unconnected-(SW13-Pad1)") (class "Default")
      (node (ref "SW13") (pin "1") (pinfunction "1_1") (pintype "passive"))
    )
    (net (code "90") (name "unconnected-(SW13-Pad4)") (class "Default")
      (node (ref "SW13") (pin "4") (pinfunction "4_4") (pintype "passive"))
    )
    (net (code "91") (name "unconnected-(SW14-Pad1)") (class "Default")
      (node (ref "SW14") (pin "1") (pinfunction "1_1") (pintype "passive"))
    )
    (net (code "92") (name "unconnected-(SW14-Pad4)") (class "Default")
      (node (ref "SW14") (pin "4") (pinfunction "4_4") (pintype "passive"))
    )
    (net (code "93") (name "unconnected-(SW15-Pad1)") (class "Default")
      (node (ref "SW15") (pin "1") (pinfunction "1_1") (pintype "passive"))
    )
    (net (code "94") (name "unconnected-(SW15-Pad4)") (class "Default")
      (node (ref "SW15") (pin "4") (pinfunction "4_4") (pintype "passive"))
    )
    (net (code "95") (name "unconnected-(SW16-Pad1)") (class "Default")
      (node (ref "SW16") (pin "1") (pinfunction "1_1") (pintype "passive"))
    )
    (net (code "96") (name "unconnected-(SW16-Pad4)") (class "Default")
      (node (ref "SW16") (pin "4") (pinfunction "4_4") (pintype "passive"))
    )
    (net (code "97") (name "unconnected-(SW17-Pad1)") (class "Default")
      (node (ref "SW17") (pin "1") (pinfunction "1_1") (pintype "passive"))
    )
    (net (code "98") (name "unconnected-(SW17-Pad4)") (class "Default")
      (node (ref "SW17") (pin "4") (pinfunction "4_4") (pintype "passive"))
    )
    (net (code "99") (name "unconnected-(SW18-Pad1)") (class "Default")
      (node (ref "SW18") (pin "1") (pinfunction "1_1") (pintype "passive"))
    )
    (net (code "100") (name "unconnected-(SW18-Pad4)") (class "Default")
      (node (ref "SW18") (pin "4") (pinfunction "4_4") (pintype "passive"))
    )
    (net (code "101") (name "unconnected-(SW19-Pad1)") (class "Default")
      (node (ref "SW19") (pin "1") (pinfunction "1_1") (pintype "passive"))
    )
    (net (code "102") (name "unconnected-(SW19-Pad4)") (class "Default")
      (node (ref "SW19") (pin "4") (pinfunction "4_4") (pintype "passive"))
    )
    (net (code "103") (name "unconnected-(SW20-Pad1)") (class "Default")
      (node (ref "SW20") (pin "1") (pinfunction "1_1") (pintype "passive"))
    )
    (net (code "104") (name "unconnected-(SW20-Pad4)") (class "Default")
      (node (ref "SW20") (pin "4") (pinfunction "4_4") (pintype "passive"))
    )
    (net (code "105") (name "unconnected-(SW21-Pad1)") (class "Default")
      (node (ref "SW21") (pin "1") (pinfunction "1_1") (pintype "passive"))
    )
    (net (code "106") (name "unconnected-(SW21-Pad4)") (class "Default")
      (node (ref "SW21") (pin "4") (pinfunction "4_4") (pintype "passive"))
    )
  )
)
